# Sexy_Rodent.net
KiCad netlist of a schematic drawn in Altium Designer
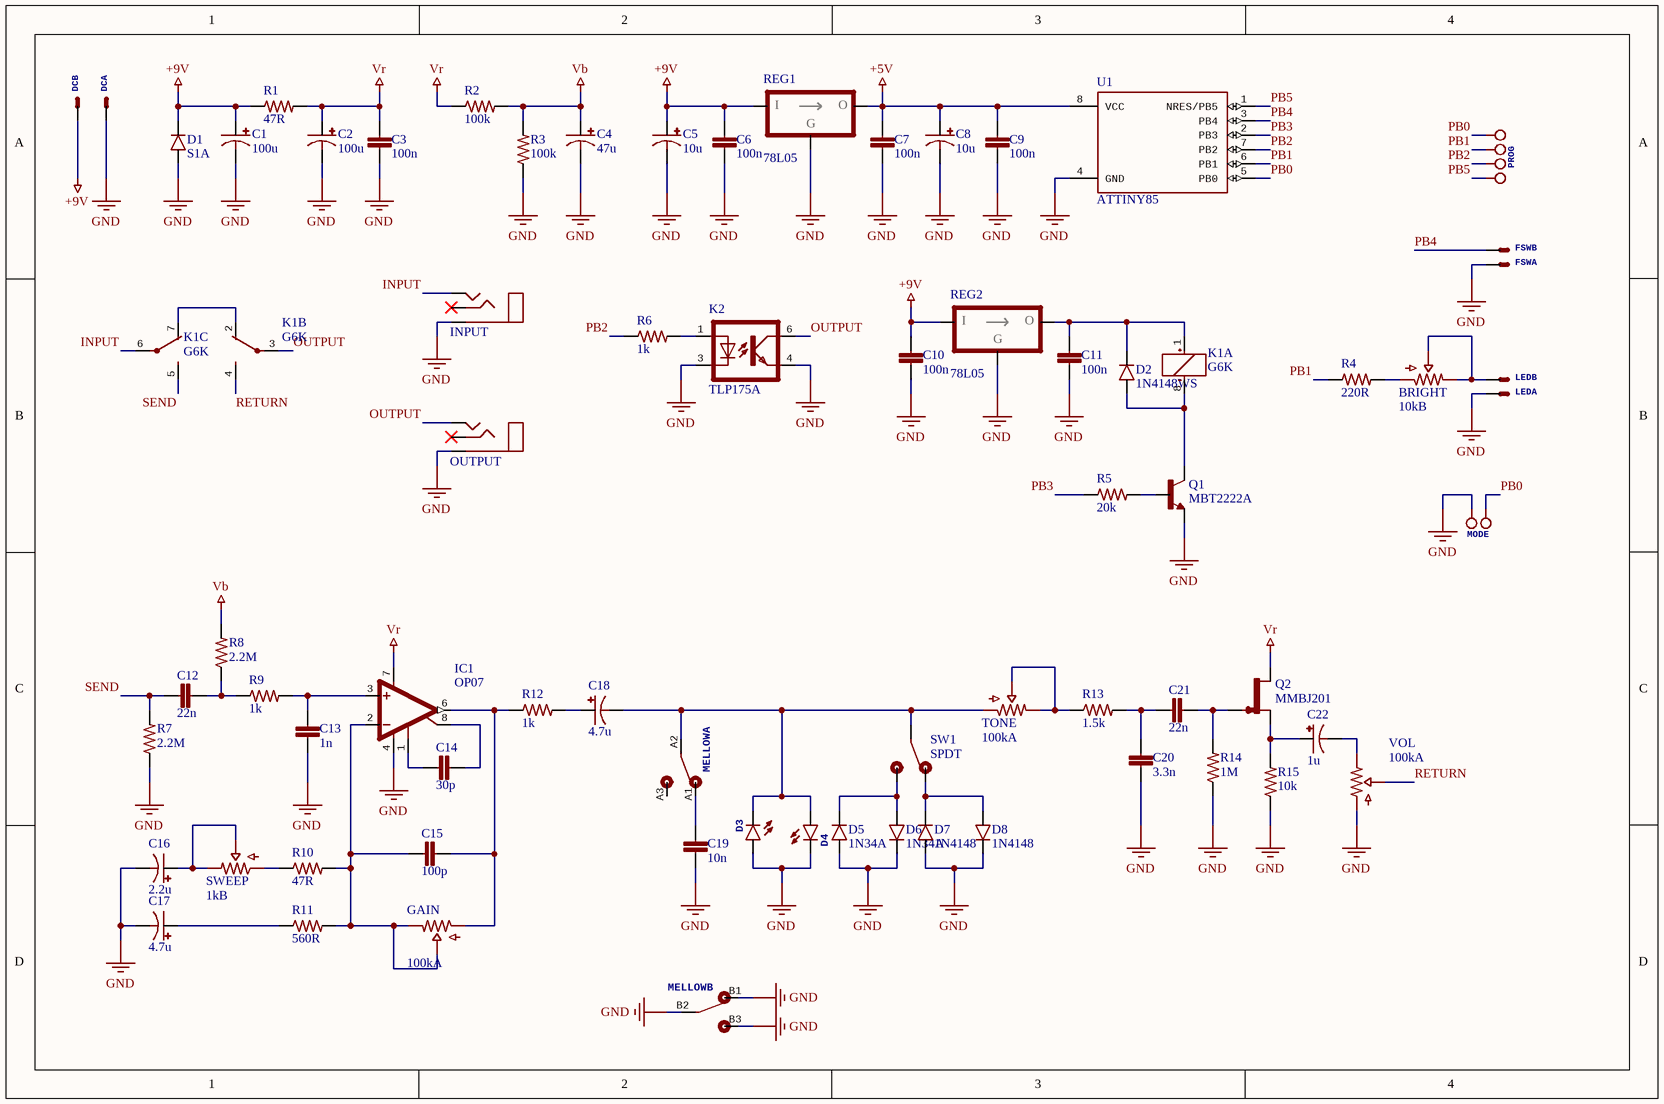
[diagram p0: Sexy Rodent.SchDoc]

(export (version "E")
  (design (tool "Eeschema 10.0.6"))
  (components
    (comp (ref "BRIGHT")
      (value "10kB")
      (footprint "BOURNS_3362P")
      (description "10k Lin 3362P trimmer")
      (libsource (lib "Pedals") (part "TRIM_10kB_3362P"))
    )
    (comp (ref "C1")
      (value "100u")
      (footprint "CAPAE_D")
      (description "CAP ALUM 100UF 25V SMD")
      (fields
        (field (name "MANUFACTURER") "Multicomp")
        (field (name "MANUFACTURER PART NUMBER") "MCVVT025M101EA6L")
      )
      (libsource (lib "Pedals SMD") (part "MCVVT025M101EA6L"))
    )
    (comp (ref "C2")
      (value "100u")
      (footprint "CAPAE_D")
      (description "CAP ALUM 100UF 25V SMD")
      (fields
        (field (name "MANUFACTURER") "Multicomp")
        (field (name "MANUFACTURER PART NUMBER") "MCVVT025M101EA6L")
      )
      (libsource (lib "Pedals SMD") (part "MCVVT025M101EA6L"))
    )
    (comp (ref "C3")
      (value "100n")
      (footprint "CHIP_0603")
      (description "CAP CER 100NF 50V X7R 0603")
      (fields
        (field (name "MANUFACTURER") "Multicomp")
        (field (name "MANUFACTURER PART NUMBER") "MC0603B104K500CT")
      )
      (libsource (lib "Pedals SMD") (part "MC0603B104K500CT"))
    )
    (comp (ref "C4")
      (value "47u")
      (footprint "CAPAE_D")
      (description "CAP ALUM 47UF 25V SMD")
      (fields
        (field (name "MANUFACTURER") "Multicomp")
        (field (name "MANUFACTURER PART NUMBER") "MCVVT025M470EA1L")
      )
      (libsource (lib "Pedals SMD") (part "MCVVT025M470EA1L"))
    )
    (comp (ref "C5")
      (value "10u")
      (footprint "CAPAE_B")
      (description "CAP ALUM 10UF 25V SMD")
      (fields
        (field (name "MANUFACTURER") "Multicomp")
        (field (name "MANUFACTURER PART NUMBER") "MCVVT025M100CA1L")
      )
      (libsource (lib "Pedals SMD") (part "MCVVT025M100CA1L"))
    )
    (comp (ref "C6")
      (value "100n")
      (footprint "CHIP_0603")
      (description "CAP CER 100NF 50V X7R 0603")
      (fields
        (field (name "MANUFACTURER") "Multicomp")
        (field (name "MANUFACTURER PART NUMBER") "MC0603B104K500CT")
      )
      (libsource (lib "Pedals SMD") (part "MC0603B104K500CT"))
    )
    (comp (ref "C7")
      (value "100n")
      (footprint "CHIP_0603")
      (description "CAP CER 100NF 50V X7R 0603")
      (fields
        (field (name "MANUFACTURER") "Multicomp")
        (field (name "MANUFACTURER PART NUMBER") "MC0603B104K500CT")
      )
      (libsource (lib "Pedals SMD") (part "MC0603B104K500CT"))
    )
    (comp (ref "C8")
      (value "10u")
      (footprint "CAPAE_B")
      (description "CAP ALUM 10UF 25V SMD")
      (fields
        (field (name "MANUFACTURER") "Multicomp")
        (field (name "MANUFACTURER PART NUMBER") "MCVVT025M100CA1L")
      )
      (libsource (lib "Pedals SMD") (part "MCVVT025M100CA1L"))
    )
    (comp (ref "C9")
      (value "100n")
      (footprint "CHIP_0603")
      (description "CAP CER 100NF 50V X7R 0603")
      (fields
        (field (name "MANUFACTURER") "Multicomp")
        (field (name "MANUFACTURER PART NUMBER") "MC0603B104K500CT")
      )
      (libsource (lib "Pedals SMD") (part "MC0603B104K500CT"))
    )
    (comp (ref "C10")
      (value "100n")
      (footprint "CHIP_0603")
      (description "CAP CER 100NF 50V X7R 0603")
      (fields
        (field (name "MANUFACTURER") "Multicomp")
        (field (name "MANUFACTURER PART NUMBER") "MC0603B104K500CT")
      )
      (libsource (lib "Pedals SMD") (part "MC0603B104K500CT"))
    )
    (comp (ref "C11")
      (value "100n")
      (footprint "CHIP_0603")
      (description "CAP CER 100NF 50V X7R 0603")
      (fields
        (field (name "MANUFACTURER") "Multicomp")
        (field (name "MANUFACTURER PART NUMBER") "MC0603B104K500CT")
      )
      (libsource (lib "Pedals SMD") (part "MC0603B104K500CT"))
    )
    (comp (ref "C12")
      (value "22n")
      (footprint "CHIP_0805")
      (description "CAP CER 22NF 50V C0G/NP0 0805")
      (fields
        (field (name "MANUFACTURER") "Murata")
        (field (name "MANUFACTURER PART NUMBER") "GRM21B5C1H223JA01L")
      )
      (libsource (lib "Pedals SMD") (part "GRM21B5C1H223JA01L"))
    )
    (comp (ref "C13")
      (value "1n")
      (footprint "CHIP_0603")
      (description "CAP CER 1NF 50V C0G/NP0 0603")
      (fields
        (field (name "MANUFACTURER") "Murata")
        (field (name "MANUFACTURER PART NUMBER") "GRM1885C1H102JA01D")
      )
      (libsource (lib "Pedals SMD") (part "GRM1885C1H102JA01D"))
    )
    (comp (ref "C14")
      (value "30p")
      (footprint "CHIP_0603")
      (description "CAP CER 30PF 50V C0G/NP0 0603")
      (fields
        (field (name "MANUFACTURER") "Multicomp")
        (field (name "MANUFACTURER PART NUMBER") "MC0603N300J500CT")
      )
      (libsource (lib "Pedals SMD") (part "MC0603N300J500CT"))
    )
    (comp (ref "C15")
      (value "100p")
      (footprint "CHIP_0603")
      (description "CAP CER 100PF 50V C0G/NP0 0603")
      (fields
        (field (name "MANUFACTURER") "Multicomp")
        (field (name "MANUFACTURER PART NUMBER") "MC0603N101J500CT")
      )
      (libsource (lib "Pedals SMD") (part "MC0603N101J500CT"))
    )
    (comp (ref "C16")
      (value "2.2u")
      (footprint "CAPAE_B")
      (description "CAP ALUM 2.2UF 20% 50V LESR SMD")
      (fields
        (field (name "MANUFACTURER") "Panasonic")
        (field (name "MANUFACTURER PART NUMBER") "EEEFC1H2R2R")
      )
      (libsource (lib "Pedals SMD") (part "EEEFC1H2R2R"))
    )
    (comp (ref "C17")
      (value "4.7u")
      (footprint "CAPAE_C")
      (description "CAP ALUM 4.7UF 50V LESR SMD")
      (fields
        (field (name "MANUFACTURER") "Panasonic")
        (field (name "MANUFACTURER PART NUMBER") "EEEFC1H4R7R")
      )
      (libsource (lib "Pedals SMD") (part "EEEFC1H4R7R"))
    )
    (comp (ref "C18")
      (value "4.7u")
      (footprint "CAPAE_C")
      (description "CAP ALUM 4.7UF 50V LESR SMD")
      (fields
        (field (name "MANUFACTURER") "Panasonic")
        (field (name "MANUFACTURER PART NUMBER") "EEEFC1H4R7R")
      )
      (libsource (lib "") (part "EEEFC1H4R7R_1"))
    )
    (comp (ref "C19")
      (value "10n")
      (footprint "CHIP_0603")
      (description "CAP CER 10NF 50V C0G/NP0 0603")
      (fields
        (field (name "MANUFACTURER") "Murata")
        (field (name "MANUFACTURER PART NUMBER") "GRM1885C1H103JA01D")
      )
      (libsource (lib "Pedals SMD") (part "GRM1885C1H103JA01D"))
    )
    (comp (ref "C20")
      (value "3.3n")
      (footprint "CHIP_0603")
      (description "CAP CER 3.3NF 50V C0G/NP0 0603")
      (fields
        (field (name "MANUFACTURER") "Murata")
        (field (name "MANUFACTURER PART NUMBER") "GRM1885C1H332JA01D")
      )
      (libsource (lib "Pedals SMD") (part "GRM1885C1H332JA01D"))
    )
    (comp (ref "C21")
      (value "22n")
      (footprint "CHIP_0805")
      (description "CAP CER 22NF 50V C0G/NP0 0805")
      (fields
        (field (name "MANUFACTURER") "Murata")
        (field (name "MANUFACTURER PART NUMBER") "GRM21B5C1H223JA01L")
      )
      (libsource (lib "Pedals SMD") (part "GRM21B5C1H223JA01L"))
    )
    (comp (ref "C22")
      (value "1u")
      (footprint "CAPAE_B")
      (description "CAP ALUM 1UF 50V LESR SMD")
      (fields
        (field (name "MANUFACTURER") "Panasonic")
        (field (name "MANUFACTURER PART NUMBER") "EEEFC1H1R0R")
      )
      (libsource (lib "Pedals SMD") (part "EEEFC1H1R0R"))
    )
    (comp (ref "D1")
      (value "S1A")
      (footprint "DO214")
      (description "DIODE GEN PURP 50V 1A SMA")
      (fields (field (name "MANUFACTURER") "ON Semiconductor / Fairchild"))
      (libsource (lib "Pedals SMD") (part "S1A"))
    )
    (comp (ref "D2")
      (value "1N4148WS")
      (footprint "SOD323")
      (description "DIODE GEN PURP 75V 150MA SOD323F")
      (fields (field (name "MANUFACTURER") "ON Semiconductor / Fairchild"))
      (libsource (lib "Pedals SMD") (part "1N4148WS"))
    )
    (comp (ref "D3")
      (value "D_LED")
      (footprint "LED_3MM")
      (description "LED")
      (libsource (lib "Pedals") (part "D_LED"))
    )
    (comp (ref "D4")
      (value "D_LED")
      (footprint "LED_3MM")
      (description "LED")
      (libsource (lib "Pedals") (part "D_LED"))
    )
    (comp (ref "D5") (value "1N34A") (footprint "DO7_4") (libsource (lib "Pedals") (part "D_1N34A")))
    (comp (ref "D6") (value "1N34A") (footprint "DO7_4") (libsource (lib "Pedals") (part "D_1N34A")))
    (comp (ref "D7") (value "1N4148") (footprint "DO35_2") (libsource (lib "Pedals") (part "D_1N4148")))
    (comp (ref "D8") (value "1N4148") (footprint "DO35_2") (libsource (lib "Pedals") (part "D_1N4148")))
    (comp (ref "DC")
      (value "J_JST-XH-02")
      (footprint "JST-XH-02")
      (description "2 Pins male XH header")
      (libsource (lib "Pedals") (part "J_JST-XH-02"))
    )
    (comp (ref "FSW")
      (value "J_JST-XH-02")
      (footprint "JST-XH-02")
      (description "2 Pins male XH header")
      (libsource (lib "Pedals") (part "J_JST-XH-02"))
    )
    (comp (ref "GAIN")
      (value "100kA")
      (footprint "ALPHA_16mm_BOTTOM")
      (description "100k Log potentiometer round shaft")
      (libsource (lib "Pedals") (part "POT_100kA_ALPHA_16mm"))
    )
    (comp (ref "IC1")
      (value "OP07")
      (footprint "SO-8")
      (description "IC OPAMP GP 600KHZ 8SOIC")
      (fields
        (field (name "MANUFACTURER") "Texas Instruments")
        (field (name "MANUFACTURER PART NUMBER") "OP07CDRG4")
      )
      (libsource (lib "Pedals SMD") (part "OP07CDRG4"))
    )
    (comp (ref "INPUT")
      (value "J_STEREO")
      (footprint "STEREO")
      (description "6.35mm stereo insulated socket jack PCB mounted")
      (libsource (lib "Pedals") (part "J_STEREO"))
    )
    (comp (ref "K1")
      (value "G6K")
      (footprint "G6K")
      (description "OMRON - G6K-2F 5DC - RELAY, SIGNAL, DPDT, 30VDC, 1A")
      (fields (field (name "MANUFACTURER") "Cliff") (field (name "MANUFACTURER PART NUMBER") "G6K-2F5DC"))
      (libsource (lib "") (part "G6K-2F5DC_2"))
    )
    (comp (ref "K2")
      (value "TLP175A")
      (footprint "TLP175A")
      (description "Toshiba TLP175A AC Input MOSFET Output Optocoupler, Surface Mount, 4-Pin SOIC")
      (fields (field (name "MANUFACTURER") "Toshiba"))
      (libsource (lib "Pedals SMD") (part "TLP175A"))
    )
    (comp (ref "LED")
      (value "J_JST-XH-02")
      (footprint "JST-XH-02")
      (description "2 Pins male XH header")
      (libsource (lib "Pedals") (part "J_JST-XH-02"))
    )
    (comp (ref "MELLOW")
      (value "DPDT")
      (footprint "DPDT_SLIDE")
      (description "DPDT slide switch ON/ON")
      (libsource (lib "Pedals") (part "SW_SLIDE_DPDT_ON-ON"))
    )
    (comp (ref "MODE")
      (value "~")
      (footprint "HEADER_2PINS")
      (description "2 Pins male header")
      (libsource (lib "Pedals") (part "J_HEADER_2PINS"))
    )
    (comp (ref "OUTPUT")
      (value "J_STEREO")
      (footprint "STEREO")
      (description "6.35mm stereo insulated socket jack PCB mounted")
      (libsource (lib "Pedals") (part "J_STEREO"))
    )
    (comp (ref "PROG")
      (value "J_HEADER_4PINS_FEM")
      (footprint "HEADER_4Pins_FEM")
      (description "4 Pins female header")
      (libsource (lib "Pedals") (part "J_HEADER_4PINS_FEM"))
    )
    (comp (ref "Q1")
      (value "MBT2222A")
      (footprint "SOT323")
      (description "TRANS NPN 40V 0.6A SOT323")
      (fields
        (field (name "MANUFACTURER") "ON Semiconductor")
        (field (name "MANUFACTURER PART NUMBER") "MMBT2222AWT1G")
      )
      (libsource (lib "Pedals SMD") (part "MMBT2222AWT1G"))
    )
    (comp (ref "Q2")
      (value "MMBJ201")
      (footprint "SOT23")
      (description "JFET N-CH 40V 350MW SOT23")
      (fields
        (field (name "MANUFACTURER") "ON Semiconductor / Fairchild")
        (field (name "MANUFACTURER PART NUMBER") "MMBFJ201")
      )
      (libsource (lib "Pedals SMD") (part "MMBFJ201"))
    )
    (comp (ref "R1")
      (value "47R")
      (footprint "CHIP_R_1206")
      (description "RES SMD 47 OHM 1% 1/4W 1206")
      (fields
        (field (name "MANUFACTURER") "Vishay")
        (field (name "MANUFACTURER PART NUMBER") "CRCW120647R0FKEA")
      )
      (libsource (lib "Pedals SMD") (part "CRCW120647R0FKEA"))
    )
    (comp (ref "R2")
      (value "100k")
      (footprint "CHIP_R_1206")
      (description "RES SMD 100K OHM 1% 1/4W 1206")
      (fields
        (field (name "MANUFACTURER") "Vishay")
        (field (name "MANUFACTURER PART NUMBER") "CRCW1206100KFKEA")
      )
      (libsource (lib "Pedals SMD") (part "CRCW1206100KFKEA"))
    )
    (comp (ref "R3")
      (value "100k")
      (footprint "CHIP_R_1206")
      (description "RES SMD 100K OHM 1% 1/4W 1206")
      (fields
        (field (name "MANUFACTURER") "Vishay")
        (field (name "MANUFACTURER PART NUMBER") "CRCW1206100KFKEA")
      )
      (libsource (lib "Pedals SMD") (part "CRCW1206100KFKEA"))
    )
    (comp (ref "R4")
      (value "220R")
      (footprint "CHIP_R_1206")
      (description "RES SMD 220 OHM 1% 1/4W 1206")
      (fields
        (field (name "MANUFACTURER") "Vishay")
        (field (name "MANUFACTURER PART NUMBER") "CRCW1206220RFKEA")
      )
      (libsource (lib "Pedals SMD") (part "CRCW1206220RFKEA"))
    )
    (comp (ref "R5")
      (value "20k")
      (footprint "CHIP_R_0603")
      (description "RES SMD 20K OHM 1% 1/10W 0603")
      (fields
        (field (name "MANUFACTURER") "Vishay")
        (field (name "MANUFACTURER PART NUMBER") "CRCW060320K0FKEA")
      )
      (libsource (lib "Pedals SMD") (part "CRCW060320K0FKEA"))
    )
    (comp (ref "R6")
      (value "1k")
      (footprint "CHIP_R_0603")
      (description "RES SMD 1K OHM 1% 1/10W 0603")
      (fields
        (field (name "MANUFACTURER") "Vishay Dale")
        (field (name "MANUFACTURER PART NUMBER") "CRCW06031K00FKEA")
      )
      (libsource (lib "Pedals SMD") (part "CRCW06031K00FKEA"))
    )
    (comp (ref "R7")
      (value "2.2M")
      (footprint "CHIP_R_0603")
      (description "RES SMD 2.2M OHM 1% 1/10W 0603")
      (fields
        (field (name "MANUFACTURER") "Vishay")
        (field (name "MANUFACTURER PART NUMBER") "CRCW06032M20FKEA")
      )
      (libsource (lib "Pedals SMD") (part "CRCW06032M20FKEA"))
    )
    (comp (ref "R8")
      (value "2.2M")
      (footprint "CHIP_R_0603")
      (description "RES SMD 2.2M OHM 1% 1/10W 0603")
      (fields
        (field (name "MANUFACTURER") "Vishay")
        (field (name "MANUFACTURER PART NUMBER") "CRCW06032M20FKEA")
      )
      (libsource (lib "Pedals SMD") (part "CRCW06032M20FKEA"))
    )
    (comp (ref "R9")
      (value "1k")
      (footprint "CHIP_R_0603")
      (description "RES SMD 1K OHM 1% 1/10W 0603")
      (fields
        (field (name "MANUFACTURER") "Vishay Dale")
        (field (name "MANUFACTURER PART NUMBER") "CRCW06031K00FKEA")
      )
      (libsource (lib "Pedals SMD") (part "CRCW06031K00FKEA"))
    )
    (comp (ref "R10")
      (value "47R")
      (footprint "CHIP_R_0603")
      (description "RES SMD 47 OHM 1% 1/10W 0603")
      (fields
        (field (name "MANUFACTURER") "Vishay")
        (field (name "MANUFACTURER PART NUMBER") "CRCW060347R0FKEA")
      )
      (libsource (lib "Pedals SMD") (part "CRCW060347R0FKEA"))
    )
    (comp (ref "R11")
      (value "560R")
      (footprint "CHIP_R_0603")
      (description "RES SMD 560 OHM 1% 1/10W 0603")
      (fields
        (field (name "MANUFACTURER") "Vishay")
        (field (name "MANUFACTURER PART NUMBER") "CRCW0603560RFKEA")
      )
      (libsource (lib "Pedals SMD") (part "CRCW0603560RFKEA"))
    )
    (comp (ref "R12")
      (value "1k")
      (footprint "CHIP_R_0603")
      (description "RES SMD 1K OHM 1% 1/10W 0603")
      (fields
        (field (name "MANUFACTURER") "Vishay Dale")
        (field (name "MANUFACTURER PART NUMBER") "CRCW06031K00FKEA")
      )
      (libsource (lib "Pedals SMD") (part "CRCW06031K00FKEA"))
    )
    (comp (ref "R13")
      (value "1.5k")
      (footprint "CHIP_R_0603")
      (description "RES SMD 1.5K OHM 1% 1/10W 0603")
      (fields
        (field (name "MANUFACTURER") "Vishay")
        (field (name "MANUFACTURER PART NUMBER") "CRCW06031K50FKEA")
      )
      (libsource (lib "Pedals SMD") (part "CRCW06031K50FKEA"))
    )
    (comp (ref "R14")
      (value "1M")
      (footprint "CHIP_R_0603")
      (description "RES SMD 1M OHM 1% 1/10W 0603")
      (fields
        (field (name "MANUFACTURER") "Vishay")
        (field (name "MANUFACTURER PART NUMBER") "CRCW06031M00FKEA")
      )
      (libsource (lib "Pedals SMD") (part "CRCW06031M00FKEA"))
    )
    (comp (ref "R15")
      (value "10k")
      (footprint "CHIP_R_0603")
      (description "RES SMD 10K OHM 1% 1/10W 0603")
      (fields
        (field (name "MANUFACTURER") "Vishay")
        (field (name "MANUFACTURER PART NUMBER") "CRCW060310K0FKEA")
      )
      (libsource (lib "Pedals SMD") (part "CRCW060310K0FKEA"))
    )
    (comp (ref "REG1")
      (value "78L05")
      (footprint "SOT23-3")
      (description "TAIWAN SEMICONDUCTOR - TS78L05CX RFG - REG 3-TERMINAL 100MA, SMD, SOT23-3")
      (fields
        (field (name "MANUFACTURER") "Taiwan Semiconductor")
        (field (name "MANUFACTURER PART NUMBER") "TS78L05CXRFG")
      )
      (libsource (lib "Pedals SMD") (part "TS78L05CXRFG"))
    )
    (comp (ref "REG2")
      (value "78L05")
      (footprint "SOT23-3")
      (description "TAIWAN SEMICONDUCTOR - TS78L05CX RFG - REG 3-TERMINAL 100MA, SMD, SOT23-3")
      (fields
        (field (name "MANUFACTURER") "Taiwan Semiconductor")
        (field (name "MANUFACTURER PART NUMBER") "TS78L05CXRFG")
      )
      (libsource (lib "Pedals SMD") (part "TS78L05CXRFG"))
    )
    (comp (ref "SW1")
      (value "SPDT")
      (footprint "SPDT")
      (description "SPDT toggle switch ON/OFF/ON")
      (libsource (lib "Pedals") (part "SW_SPDT_ON-OFF-ON"))
    )
    (comp (ref "SWEEP")
      (value "1kB")
      (footprint "ALPHA_16mm_BOTTOM")
      (description "1k Lin potentiometer round shaft")
      (libsource (lib "Pedals") (part "POT_1kB_ALPHA_16mm"))
    )
    (comp (ref "TONE")
      (value "100kA")
      (footprint "ALPHA_16mm_BOTTOM")
      (description "100k Log potentiometer round shaft")
      (libsource (lib "Pedals") (part "POT_100kA_ALPHA_16mm"))
    )
    (comp (ref "U1")
      (value "ATTINY85")
      (footprint "SOP8")
      (description "IC, 8BIT MCU, AVR TINY, 20MHZ, 8-SOIC")
      (fields
        (field (name "MANUFACTURER") "Microchip / Atmel")
        (field (name "MANUFACTURER PART NUMBER") "ATTINY85-20SU")
      )
      (libsource (lib "Pedals SMD") (part "ATTINY85-20SU"))
    )
    (comp (ref "VOL")
      (value "100kA")
      (footprint "ALPHA_16mm_BOTTOM")
      (description "100k Log potentiometer round shaft")
      (libsource (lib "Pedals") (part "POT_100kA_ALPHA_16mm"))
    )
  )
  (nets
    (net (code "1") (name "+5V") (class "Default")
      (node (ref "C7") (pin "1") (pinfunction "1_1") (pintype "passive"))
      (node (ref "C8") (pin "+") (pinfunction "+_+") (pintype "passive"))
      (node (ref "C9") (pin "1") (pinfunction "1_1") (pintype "passive"))
      (node (ref "REG1") (pin "1") (pinfunction "OUTPUT_1") (pintype "power_in"))
      (node (ref "U1") (pin "8") (pinfunction "VCC_8") (pintype "power_in"))
    )
    (net (code "2") (name "+9V") (class "Default")
      (node (ref "C1") (pin "+") (pinfunction "+_+") (pintype "passive"))
      (node (ref "C10") (pin "1") (pinfunction "1_1") (pintype "passive"))
      (node (ref "C5") (pin "+") (pinfunction "+_+") (pintype "passive"))
      (node (ref "C6") (pin "1") (pinfunction "1_1") (pintype "passive"))
      (node (ref "D1") (pin "1") (pinfunction "1_1") (pintype "passive"))
      (node (ref "DC") (pin "1") (pinfunction "S_1") (pintype "passive"))
      (node (ref "R1") (pin "1") (pinfunction "1_1") (pintype "passive"))
      (node (ref "REG1") (pin "2") (pinfunction "INPUT_2") (pintype "power_in"))
      (node (ref "REG2") (pin "2") (pinfunction "INPUT_2") (pintype "power_in"))
    )
    (net (code "3") (name "/INPUT") (class "Default")
      (node (ref "INPUT") (pin "T") (pinfunction "T_T") (pintype "passive"))
      (node (ref "K1") (pin "6") (pinfunction "P_6") (pintype "passive"))
    )
    (net (code "4") (name "/OUTPUT") (class "Default")
      (node (ref "K1") (pin "3") (pinfunction "P_3") (pintype "passive"))
      (node (ref "K2") (pin "6") (pinfunction "COL_6") (pintype "passive"))
      (node (ref "OUTPUT") (pin "T") (pinfunction "T_T") (pintype "passive"))
    )
    (net (code "5") (name "/PB0") (class "Default")
      (node (ref "MODE") (pin "2") (pinfunction "2_2") (pintype "passive"))
      (node (ref "PROG") (pin "4") (pinfunction "4_4") (pintype "passive"))
      (node (ref "U1") (pin "5") (pinfunction "PB0_5") (pintype "bidirectional"))
    )
    (net (code "6") (name "/PB1") (class "Default")
      (node (ref "PROG") (pin "3") (pinfunction "3_3") (pintype "passive"))
      (node (ref "R4") (pin "1") (pinfunction "1_1") (pintype "passive"))
      (node (ref "U1") (pin "6") (pinfunction "PB1_6") (pintype "bidirectional"))
    )
    (net (code "7") (name "/PB2") (class "Default")
      (node (ref "PROG") (pin "2") (pinfunction "2_2") (pintype "passive"))
      (node (ref "R6") (pin "1") (pinfunction "1_1") (pintype "passive"))
      (node (ref "U1") (pin "7") (pinfunction "PB2_7") (pintype "bidirectional"))
    )
    (net (code "8") (name "/PB3") (class "Default")
      (node (ref "R5") (pin "1") (pinfunction "1_1") (pintype "passive"))
      (node (ref "U1") (pin "2") (pinfunction "PB3_2") (pintype "bidirectional"))
    )
    (net (code "9") (name "/PB4") (class "Default")
      (node (ref "FSW") (pin "1") (pinfunction "S_1") (pintype "passive"))
      (node (ref "U1") (pin "3") (pinfunction "PB4_3") (pintype "bidirectional"))
    )
    (net (code "10") (name "/PB5") (class "Default")
      (node (ref "PROG") (pin "1") (pinfunction "1_1") (pintype "passive"))
      (node (ref "U1") (pin "1") (pinfunction "NRES/PB5_1") (pintype "bidirectional"))
    )
    (net (code "11") (name "/RETURN") (class "Default")
      (node (ref "K1") (pin "4") (pinfunction "S_4") (pintype "passive"))
      (node (ref "VOL") (pin "2") (pinfunction "2_2") (pintype "passive"))
    )
    (net (code "12") (name "/SEND") (class "Default")
      (node (ref "C12") (pin "2") (pinfunction "2_2") (pintype "passive"))
      (node (ref "K1") (pin "5") (pinfunction "S_5") (pintype "passive"))
      (node (ref "R7") (pin "2") (pinfunction "2_2") (pintype "passive"))
    )
    (net (code "13") (name "GND") (class "Default")
      (node (ref "C1") (pin "-") (pinfunction "-_-") (pintype "passive"))
      (node (ref "C10") (pin "2") (pinfunction "2_2") (pintype "passive"))
      (node (ref "C11") (pin "2") (pinfunction "2_2") (pintype "passive"))
      (node (ref "C13") (pin "2") (pinfunction "2_2") (pintype "passive"))
      (node (ref "C16") (pin "-") (pinfunction "-_-") (pintype "passive"))
      (node (ref "C17") (pin "-") (pinfunction "-_-") (pintype "passive"))
      (node (ref "C19") (pin "2") (pinfunction "2_2") (pintype "passive"))
      (node (ref "C2") (pin "-") (pinfunction "-_-") (pintype "passive"))
      (node (ref "C20") (pin "2") (pinfunction "2_2") (pintype "passive"))
      (node (ref "C3") (pin "2") (pinfunction "2_2") (pintype "passive"))
      (node (ref "C4") (pin "-") (pinfunction "-_-") (pintype "passive"))
      (node (ref "C5") (pin "-") (pinfunction "-_-") (pintype "passive"))
      (node (ref "C6") (pin "2") (pinfunction "2_2") (pintype "passive"))
      (node (ref "C7") (pin "2") (pinfunction "2_2") (pintype "passive"))
      (node (ref "C8") (pin "-") (pinfunction "-_-") (pintype "passive"))
      (node (ref "C9") (pin "2") (pinfunction "2_2") (pintype "passive"))
      (node (ref "D1") (pin "2") (pinfunction "2_2") (pintype "passive"))
      (node (ref "D3") (pin "ANODE") (pinfunction "A_ANODE") (pintype "passive"))
      (node (ref "D4") (pin "P$1") (pinfunction "C_P$1") (pintype "passive"))
      (node (ref "D5") (pin "A") (pinfunction "A_A") (pintype "passive"))
      (node (ref "D6") (pin "C") (pinfunction "C_C") (pintype "passive"))
      (node (ref "D7") (pin "A") (pinfunction "A_A") (pintype "passive"))
      (node (ref "D8") (pin "C") (pinfunction "C_C") (pintype "passive"))
      (node (ref "DC") (pin "2") (pinfunction "S_2") (pintype "passive"))
      (node (ref "FSW") (pin "2") (pinfunction "S_2") (pintype "passive"))
      (node (ref "IC1") (pin "4") (pinfunction "V-_4") (pintype "power_in"))
      (node (ref "INPUT") (pin "S") (pinfunction "S_S") (pintype "passive"))
      (node (ref "K2") (pin "3") (pinfunction "C_3") (pintype "passive"))
      (node (ref "K2") (pin "4") (pinfunction "EMIT_4") (pintype "passive"))
      (node (ref "LED") (pin "2") (pinfunction "S_2") (pintype "passive"))
      (node (ref "MELLOW") (pin "B1") (pinfunction "1_B1") (pintype "passive"))
      (node (ref "MELLOW") (pin "B2") (pinfunction "2_B2") (pintype "passive"))
      (node (ref "MELLOW") (pin "B3") (pinfunction "3_B3") (pintype "passive"))
      (node (ref "MODE") (pin "1") (pinfunction "1_1") (pintype "passive"))
      (node (ref "OUTPUT") (pin "S") (pinfunction "S_S") (pintype "passive"))
      (node (ref "Q1") (pin "2") (pinfunction "E_2") (pintype "passive"))
      (node (ref "R14") (pin "1") (pinfunction "1_1") (pintype "passive"))
      (node (ref "R15") (pin "1") (pinfunction "1_1") (pintype "passive"))
      (node (ref "R3") (pin "1") (pinfunction "1_1") (pintype "passive"))
      (node (ref "R7") (pin "1") (pinfunction "1_1") (pintype "passive"))
      (node (ref "REG1") (pin "3") (pinfunction "COMMON_3") (pintype "power_in"))
      (node (ref "REG2") (pin "3") (pinfunction "COMMON_3") (pintype "power_in"))
      (node (ref "U1") (pin "4") (pinfunction "GND_4") (pintype "power_in"))
      (node (ref "VOL") (pin "1") (pinfunction "1_1") (pintype "passive"))
    )
    (net (code "14") (name "Net-(BRIGHT-Pad1)") (class "Default")
      (node (ref "BRIGHT") (pin "1") (pinfunction "1_1") (pintype "passive"))
      (node (ref "R4") (pin "2") (pinfunction "2_2") (pintype "passive"))
    )
    (net (code "15") (name "Net-(C12-Pad1)") (class "Default")
      (node (ref "C12") (pin "1") (pinfunction "1_1") (pintype "passive"))
      (node (ref "R8") (pin "1") (pinfunction "1_1") (pintype "passive"))
      (node (ref "R9") (pin "1") (pinfunction "1_1") (pintype "passive"))
    )
    (net (code "16") (name "Net-(C16-Pad+)") (class "Default")
      (node (ref "C16") (pin "+") (pinfunction "+_+") (pintype "passive"))
      (node (ref "SWEEP") (pin "2") (pinfunction "2_2") (pintype "passive"))
      (node (ref "SWEEP") (pin "3") (pinfunction "3_3") (pintype "passive"))
    )
    (net (code "17") (name "Net-(C17-Pad+)") (class "Default")
      (node (ref "C17") (pin "+") (pinfunction "+_+") (pintype "passive"))
      (node (ref "R11") (pin "1") (pinfunction "1_1") (pintype "passive"))
    )
    (net (code "18") (name "Net-(C18-Pad+)") (class "Default")
      (node (ref "C18") (pin "+") (pinfunction "+_+") (pintype "passive"))
      (node (ref "R12") (pin "2") (pinfunction "2_2") (pintype "passive"))
    )
    (net (code "19") (name "Net-(C20-Pad1)") (class "Default")
      (node (ref "C20") (pin "1") (pinfunction "1_1") (pintype "passive"))
      (node (ref "C21") (pin "2") (pinfunction "2_2") (pintype "passive"))
      (node (ref "R13") (pin "2") (pinfunction "2_2") (pintype "passive"))
    )
    (net (code "20") (name "Net-(C22-Pad-)") (class "Default")
      (node (ref "C22") (pin "-") (pinfunction "-_-") (pintype "passive"))
      (node (ref "VOL") (pin "3") (pinfunction "3_3") (pintype "passive"))
    )
    (net (code "21") (name "Net-(D3-C)") (class "Default")
      (node (ref "C18") (pin "-") (pinfunction "-_-") (pintype "passive"))
      (node (ref "D3") (pin "P$1") (pinfunction "C_P$1") (pintype "passive"))
      (node (ref "D4") (pin "ANODE") (pinfunction "A_ANODE") (pintype "passive"))
      (node (ref "MELLOW") (pin "A2") (pinfunction "2_A2") (pintype "passive"))
      (node (ref "SW1") (pin "2") (pinfunction "P_2") (pintype "passive"))
      (node (ref "TONE") (pin "1") (pinfunction "1_1") (pintype "passive"))
    )
    (net (code "22") (name "Net-(IC1-+IN)") (class "Default")
      (node (ref "C13") (pin "1") (pinfunction "1_1") (pintype "passive"))
      (node (ref "IC1") (pin "3") (pinfunction "+IN_3") (pintype "passive"))
      (node (ref "R9") (pin "2") (pinfunction "2_2") (pintype "passive"))
    )
    (net (code "23") (name "Net-(IC1--IN)") (class "Default")
      (node (ref "C15") (pin "2") (pinfunction "2_2") (pintype "passive"))
      (node (ref "GAIN") (pin "2") (pinfunction "2_2") (pintype "passive"))
      (node (ref "GAIN") (pin "3") (pinfunction "3_3") (pintype "passive"))
      (node (ref "IC1") (pin "2") (pinfunction "-IN_2") (pintype "passive"))
      (node (ref "R10") (pin "2") (pinfunction "2_2") (pintype "passive"))
      (node (ref "R11") (pin "2") (pinfunction "2_2") (pintype "passive"))
    )
    (net (code "24") (name "Net-(IC1-CMP1)") (class "Default")
      (node (ref "C14") (pin "2") (pinfunction "2_2") (pintype "passive"))
      (node (ref "IC1") (pin "1") (pinfunction "CMP1_1") (pintype "passive"))
    )
    (net (code "25") (name "Net-(IC1-CMP2)") (class "Default")
      (node (ref "C14") (pin "1") (pinfunction "1_1") (pintype "passive"))
      (node (ref "IC1") (pin "8") (pinfunction "CMP2_8") (pintype "passive"))
    )
    (net (code "26") (name "Net-(IC1-OUT)") (class "Default")
      (node (ref "C15") (pin "1") (pinfunction "1_1") (pintype "passive"))
      (node (ref "GAIN") (pin "1") (pinfunction "1_1") (pintype "passive"))
      (node (ref "IC1") (pin "6") (pinfunction "OUT_6") (pintype "output"))
      (node (ref "R12") (pin "1") (pinfunction "1_1") (pintype "passive"))
    )
    (net (code "27") (name "Net-(K1A-+)") (class "Default")
      (node (ref "C11") (pin "1") (pinfunction "1_1") (pintype "passive"))
      (node (ref "D2") (pin "1") (pinfunction "1_1") (pintype "passive"))
      (node (ref "K1") (pin "1") (pinfunction "+_1") (pintype "passive"))
      (node (ref "REG2") (pin "1") (pinfunction "OUTPUT_1") (pintype "power_in"))
    )
    (net (code "28") (name "Net-(K1A--)") (class "Default")
      (node (ref "D2") (pin "2") (pinfunction "2_2") (pintype "passive"))
      (node (ref "K1") (pin "8") (pinfunction "-_8") (pintype "passive"))
      (node (ref "Q1") (pin "3") (pinfunction "C_3") (pintype "passive"))
    )
    (net (code "29") (name "Net-(K1B-O)") (class "Default")
      (node (ref "K1") (pin "2") (pinfunction "O_2") (pintype "passive"))
      (node (ref "K1") (pin "7") (pinfunction "O_7") (pintype "passive"))
    )
    (net (code "30") (name "Net-(K2-A)") (class "Default")
      (node (ref "K2") (pin "1") (pinfunction "A_1") (pintype "passive"))
      (node (ref "R6") (pin "2") (pinfunction "2_2") (pintype "passive"))
    )
    (net (code "31") (name "Net-(LEDB-S)") (class "Default")
      (node (ref "BRIGHT") (pin "2") (pinfunction "2_2") (pintype "passive"))
      (node (ref "BRIGHT") (pin "3") (pinfunction "3_3") (pintype "passive"))
      (node (ref "LED") (pin "1") (pinfunction "S_1") (pintype "passive"))
    )
    (net (code "32") (name "Net-(MELLOWA-1)") (class "Default")
      (node (ref "C19") (pin "1") (pinfunction "1_1") (pintype "passive"))
      (node (ref "MELLOW") (pin "A1") (pinfunction "1_A1") (pintype "passive"))
    )
    (net (code "33") (name "Net-(Q1-B)") (class "Default")
      (node (ref "Q1") (pin "1") (pinfunction "B_1") (pintype "passive"))
      (node (ref "R5") (pin "2") (pinfunction "2_2") (pintype "passive"))
    )
    (net (code "34") (name "Net-(Q2-G)") (class "Default")
      (node (ref "C21") (pin "1") (pinfunction "1_1") (pintype "passive"))
      (node (ref "Q2") (pin "3") (pinfunction "G_3") (pintype "passive"))
      (node (ref "R14") (pin "2") (pinfunction "2_2") (pintype "passive"))
    )
    (net (code "35") (name "Net-(Q2-S)") (class "Default")
      (node (ref "C22") (pin "+") (pinfunction "+_+") (pintype "passive"))
      (node (ref "Q2") (pin "2") (pinfunction "S_2") (pintype "passive"))
      (node (ref "R15") (pin "2") (pinfunction "2_2") (pintype "passive"))
    )
    (net (code "36") (name "Net-(R10-Pad1)") (class "Default")
      (node (ref "R10") (pin "1") (pinfunction "1_1") (pintype "passive"))
      (node (ref "SWEEP") (pin "1") (pinfunction "1_1") (pintype "passive"))
    )
    (net (code "37") (name "Net-(R13-Pad1)") (class "Default")
      (node (ref "R13") (pin "1") (pinfunction "1_1") (pintype "passive"))
      (node (ref "TONE") (pin "2") (pinfunction "2_2") (pintype "passive"))
      (node (ref "TONE") (pin "3") (pinfunction "3_3") (pintype "passive"))
    )
    (net (code "38") (name "Net-(SW1-O)") (class "Default")
      (node (ref "D7") (pin "C") (pinfunction "C_C") (pintype "passive"))
      (node (ref "D8") (pin "A") (pinfunction "A_A") (pintype "passive"))
      (node (ref "SW1") (pin "1") (pinfunction "O_1") (pintype "passive"))
    )
    (net (code "39") (name "Net-(SW1-S)") (class "Default")
      (node (ref "D5") (pin "C") (pinfunction "C_C") (pintype "passive"))
      (node (ref "D6") (pin "A") (pinfunction "A_A") (pintype "passive"))
      (node (ref "SW1") (pin "3") (pinfunction "S_3") (pintype "passive"))
    )
    (net (code "40") (name "Vb") (class "Default")
      (node (ref "C4") (pin "+") (pinfunction "+_+") (pintype "passive"))
      (node (ref "R2") (pin "2") (pinfunction "2_2") (pintype "passive"))
      (node (ref "R3") (pin "2") (pinfunction "2_2") (pintype "passive"))
      (node (ref "R8") (pin "2") (pinfunction "2_2") (pintype "passive"))
    )
    (net (code "41") (name "Vr") (class "Default")
      (node (ref "C2") (pin "+") (pinfunction "+_+") (pintype "passive"))
      (node (ref "C3") (pin "1") (pinfunction "1_1") (pintype "passive"))
      (node (ref "IC1") (pin "7") (pinfunction "V+_7") (pintype "power_in"))
      (node (ref "Q2") (pin "1") (pinfunction "D_1") (pintype "passive"))
      (node (ref "R1") (pin "2") (pinfunction "2_2") (pintype "passive"))
      (node (ref "R2") (pin "1") (pinfunction "1_1") (pintype "passive"))
    )
    (net (code "42") (name "unconnected-(INPUT-PadR)") (class "Default")
      (node (ref "INPUT") (pin "R") (pinfunction "R_R") (pintype "passive+no_connect"))
    )
    (net (code "43") (name "unconnected-(MELLOWA-3-PadA3)") (class "Default")
      (node (ref "MELLOW") (pin "A3") (pinfunction "3_A3") (pintype "passive"))
    )
    (net (code "44") (name "unconnected-(OUTPUT-PadR)") (class "Default")
      (node (ref "OUTPUT") (pin "R") (pinfunction "R_R") (pintype "passive+no_connect"))
    )
  )
)
